# ESP32_base_brd.net
KiCad netlist of a schematic drawn in EAGLE
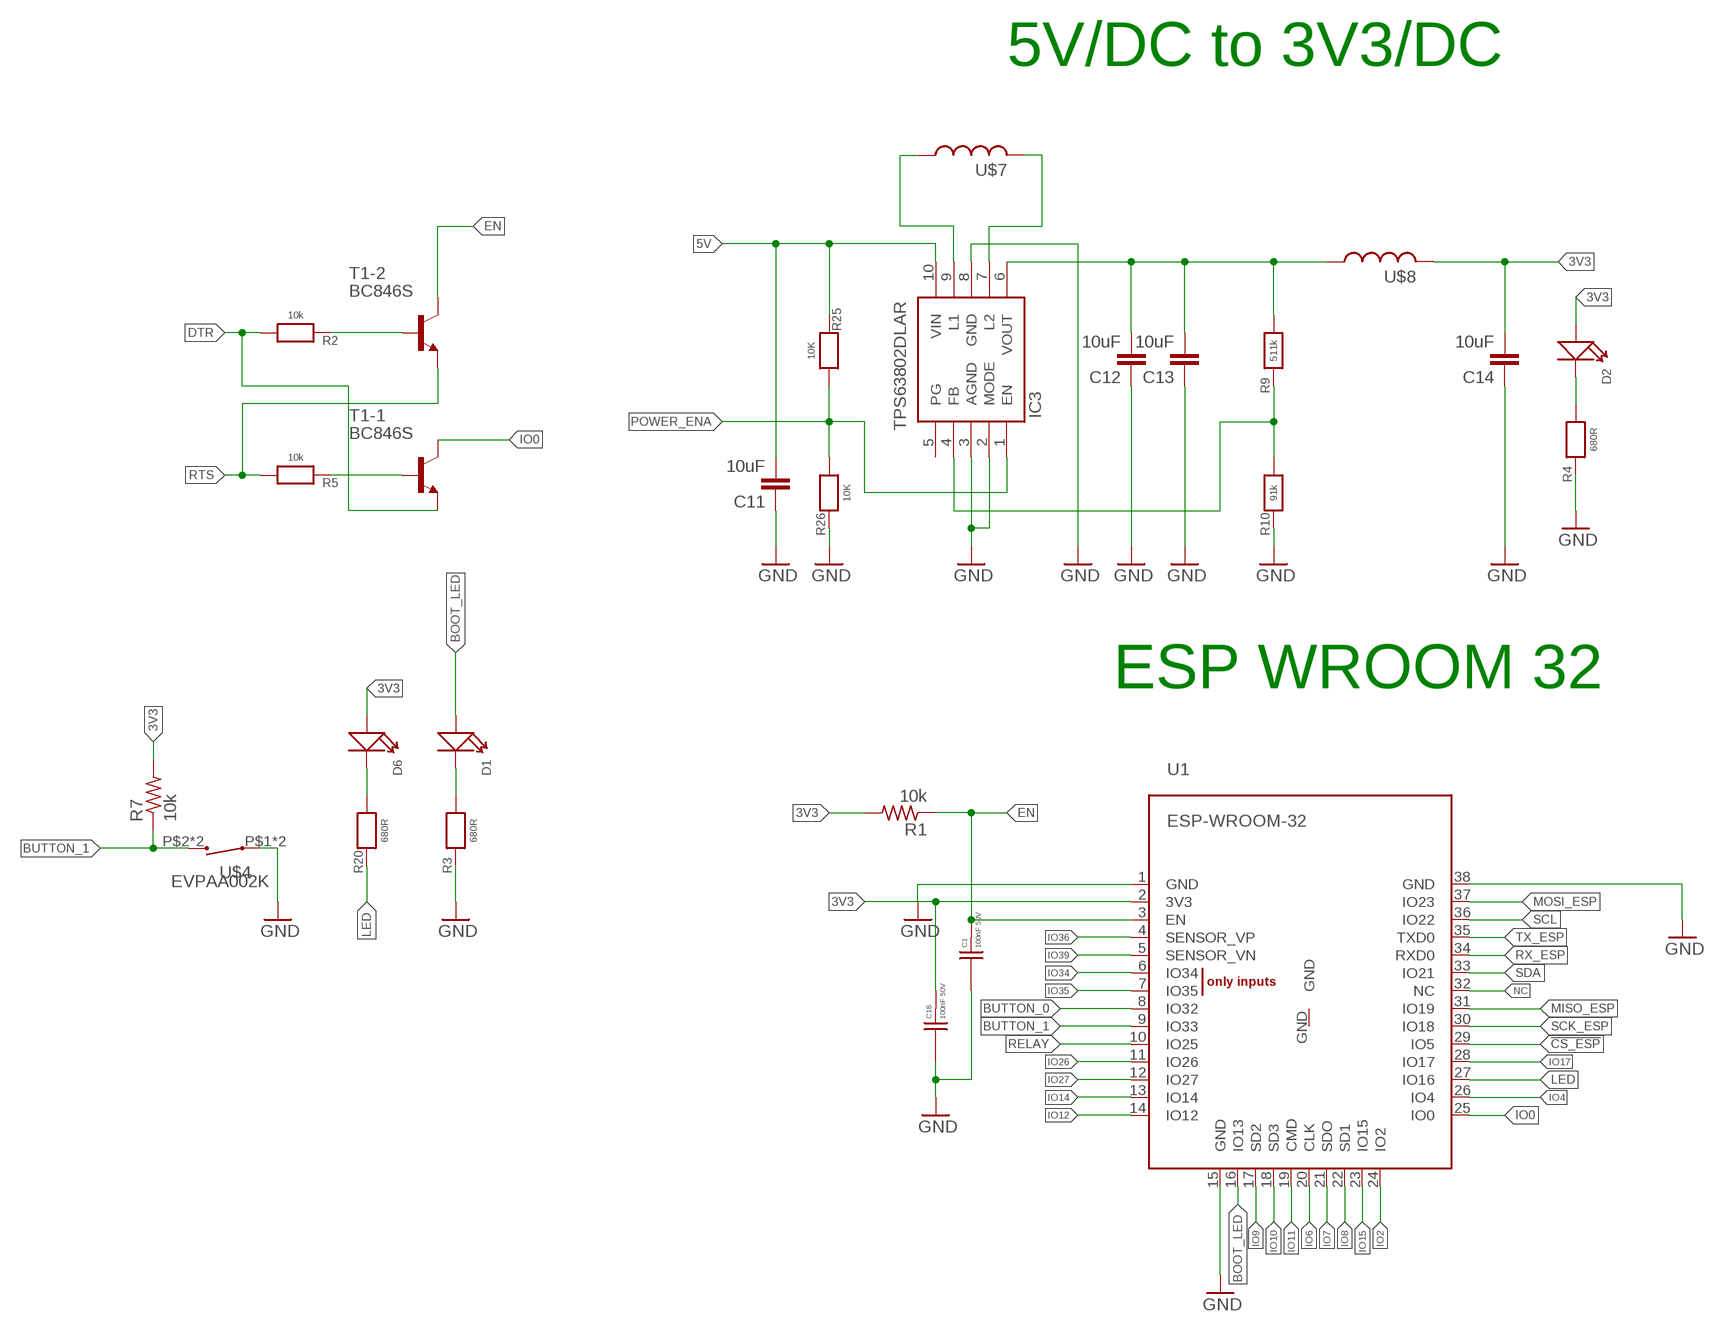
[diagram p0: schematic, sheet 1]

(export (version "E")
  (design (tool "Eeschema 10.0.6"))
  (components
    (comp (ref "C1")
      (value "100nF 50V")
      (footprint "eagle-import:0402")
      (fields (field (name "MPN") "GPC0402104"))
      (libsource (lib "eagle-import") (part "CAPACITOR_CERAMIC_0402_100NF"))
    )
    (comp (ref "C11")
      (value "10uF")
      (footprint "eagle-import:C0603")
      (libsource (lib "eagle-import") (part "C-EUC0603"))
    )
    (comp (ref "C12")
      (value "10uF")
      (footprint "eagle-import:C0603")
      (libsource (lib "eagle-import") (part "C-EUC0603"))
    )
    (comp (ref "C13")
      (value "10uF")
      (footprint "eagle-import:C0603")
      (libsource (lib "eagle-import") (part "C-EUC0603"))
    )
    (comp (ref "C14")
      (value "10uF")
      (footprint "eagle-import:C0603")
      (libsource (lib "eagle-import") (part "C-EUC0603"))
    )
    (comp (ref "C18")
      (value "100nF 50V")
      (footprint "eagle-import:0402")
      (fields (field (name "MPN") "GPC0402104"))
      (libsource (lib "eagle-import") (part "CAPACITOR_CERAMIC_0402_100NF"))
    )
    (comp (ref "D1")
      (value "SMD-LED-YELLOW-DIFFUSED-PURE-WHITE(0402)")
      (footprint "eagle-import:LED-0402")
      (fields (field (name "MPN") "16-219A/T2D-AR2T1QY/3T"))
      (libsource (lib "eagle-import") (part "SMD-LED-YELLOW-DIFFUSED-PURE-WHITE(0402)"))
    )
    (comp (ref "D2")
      (value "SMD-LED-YELLOW-DIFFUSED-PURE-WHITE(0402)")
      (footprint "eagle-import:LED-0402")
      (fields (field (name "MPN") "16-219A/T2D-AR2T1QY/3T"))
      (libsource (lib "eagle-import") (part "SMD-LED-YELLOW-DIFFUSED-PURE-WHITE(0402)"))
    )
    (comp (ref "D6")
      (value "SMD-LED-YELLOW-DIFFUSED-PURE-WHITE(0402)")
      (footprint "eagle-import:LED-0402")
      (fields (field (name "MPN") "16-219A/T2D-AR2T1QY/3T"))
      (libsource (lib "eagle-import") (part "SMD-LED-YELLOW-DIFFUSED-PURE-WHITE(0402)"))
    )
    (comp (ref "IC3")
      (value "TPS63802DLAR")
      (footprint "eagle-import:TPS63802DLAR")
      (libsource (lib "eagle-import") (part "TPS63802DLAR"))
    )
    (comp (ref "R1")
      (value "10k")
      (footprint "eagle-import:R0805")
      (libsource (lib "eagle-import") (part "R-US_R0805"))
    )
    (comp (ref "R2")
      (value "10k")
      (footprint "eagle-import:0402")
      (libsource (lib "eagle-import") (part "vb_R_EC_RESISTOR_0402"))
    )
    (comp (ref "R3")
      (value "680R")
      (footprint "eagle-import:0402")
      (libsource (lib "eagle-import") (part "vb_R_EC_RESISTOR_0402"))
    )
    (comp (ref "R4")
      (value "680R")
      (footprint "eagle-import:0402")
      (libsource (lib "eagle-import") (part "vb_R_EC_RESISTOR_0402"))
    )
    (comp (ref "R5")
      (value "10k")
      (footprint "eagle-import:0402")
      (libsource (lib "eagle-import") (part "vb_R_EC_RESISTOR_0402"))
    )
    (comp (ref "R7")
      (value "10k")
      (footprint "eagle-import:R0805")
      (libsource (lib "eagle-import") (part "R-US_R0805"))
    )
    (comp (ref "R9")
      (value "511k")
      (footprint "eagle-import:0402")
      (libsource (lib "eagle-import") (part "RESISTOR_0402"))
    )
    (comp (ref "R10")
      (value "91k")
      (footprint "eagle-import:0402")
      (libsource (lib "eagle-import") (part "RESISTOR_0402"))
    )
    (comp (ref "R20")
      (value "680R")
      (footprint "eagle-import:0402")
      (libsource (lib "eagle-import") (part "vb_R_EC_RESISTOR_0402"))
    )
    (comp (ref "R25")
      (value "10K")
      (footprint "eagle-import:0402")
      (libsource (lib "eagle-import") (part "RESISTOR_0402"))
    )
    (comp (ref "R26")
      (value "10K")
      (footprint "eagle-import:0402")
      (libsource (lib "eagle-import") (part "RESISTOR_0402"))
    )
    (comp (ref "T1")
      (value "BC846S")
      (footprint "eagle-import:SOT363")
      (fields (field (name "MF") "NXP Semiconductors"))
      (libsource (lib "eagle-import") (part "BC846S"))
    )
    (comp (ref "U$4")
      (value "EVPAA002K")
      (footprint "eagle-import:EVPAA002K")
      (libsource (lib "eagle-import") (part "EVPAA002K"))
    )
    (comp (ref "U$7")
      (value "INDUCTOR_2016")
      (footprint "eagle-import:2016")
      (libsource (lib "eagle-import") (part "INDUCTOR_2016"))
    )
    (comp (ref "U$8")
      (value "INDUCTOR_2016")
      (footprint "eagle-import:2016")
      (libsource (lib "eagle-import") (part "INDUCTOR_2016"))
    )
    (comp (ref "U1")
      (value "ESP-WROOM-32")
      (footprint "eagle-import:ESP-WROOM-32")
      (libsource (lib "eagle-import") (part "ESP-WROOM-32"))
    )
  )
  (nets
    (net (code "1") (name "/~{CS_ESP}") (class "Default")
      (node (ref "U1") (pin "29") (pinfunction "IO5_29") (pintype "bidirectional"))
    )
    (net (code "2") (name "3V3") (class "Default")
      (node (ref "C14") (pin "2") (pinfunction "2_2") (pintype "passive"))
      (node (ref "C18") (pin "2") (pinfunction "2_2") (pintype "passive"))
      (node (ref "D2") (pin "+") (pinfunction "+_+") (pintype "passive"))
      (node (ref "D6") (pin "+") (pinfunction "+_+") (pintype "passive"))
      (node (ref "R1") (pin "2") (pinfunction "2_2") (pintype "passive"))
      (node (ref "R7") (pin "2") (pinfunction "2_2") (pintype "passive"))
      (node (ref "U$8") (pin "2") (pinfunction "2_2") (pintype "passive"))
      (node (ref "U1") (pin "2") (pinfunction "3V3_2") (pintype "bidirectional"))
    )
    (net (code "3") (name "5V") (class "Default")
      (node (ref "C11") (pin "2") (pinfunction "2_2") (pintype "passive"))
      (node (ref "IC3") (pin "10") (pinfunction "VIN_10") (pintype "bidirectional"))
      (node (ref "R25") (pin "1") (pinfunction "1_1") (pintype "passive"))
    )
    (net (code "4") (name "BOOT_LED") (class "Default")
      (node (ref "D1") (pin "+") (pinfunction "+_+") (pintype "passive"))
      (node (ref "U1") (pin "16") (pinfunction "IO13_16") (pintype "bidirectional"))
    )
    (net (code "5") (name "BUTTON_0") (class "Default")
      (node (ref "U1") (pin "8") (pinfunction "IO32_8") (pintype "bidirectional"))
    )
    (net (code "6") (name "BUTTON_1") (class "Default")
      (node (ref "R7") (pin "1") (pinfunction "1_1") (pintype "passive"))
      (node (ref "U$4") (pin "P$2") (pinfunction "2_P$2") (pintype "passive"))
      (node (ref "U$4") (pin "P$4") (pinfunction "2_P$4") (pintype "passive"))
      (node (ref "U1") (pin "9") (pinfunction "IO33_9") (pintype "bidirectional"))
    )
    (net (code "7") (name "DTR") (class "Default")
      (node (ref "R2") (pin "2") (pinfunction "2_2") (pintype "passive"))
      (node (ref "T1") (pin "1") (pinfunction "E_1") (pintype "passive"))
    )
    (net (code "8") (name "EN") (class "Default")
      (node (ref "C1") (pin "2") (pinfunction "2_2") (pintype "passive"))
      (node (ref "R1") (pin "1") (pinfunction "1_1") (pintype "passive"))
      (node (ref "T1") (pin "3") (pinfunction "C_3") (pintype "passive"))
      (node (ref "U1") (pin "3") (pinfunction "EN_3") (pintype "bidirectional"))
    )
    (net (code "9") (name "GND") (class "Default")
      (node (ref "C1") (pin "1") (pinfunction "1_1") (pintype "passive"))
      (node (ref "C11") (pin "1") (pinfunction "1_1") (pintype "passive"))
      (node (ref "C12") (pin "1") (pinfunction "1_1") (pintype "passive"))
      (node (ref "C13") (pin "1") (pinfunction "1_1") (pintype "passive"))
      (node (ref "C14") (pin "1") (pinfunction "1_1") (pintype "passive"))
      (node (ref "C18") (pin "1") (pinfunction "1_1") (pintype "passive"))
      (node (ref "IC3") (pin "2") (pinfunction "MODE_2") (pintype "bidirectional"))
      (node (ref "IC3") (pin "3") (pinfunction "AGND_3") (pintype "bidirectional"))
      (node (ref "IC3") (pin "8") (pinfunction "GND_8") (pintype "bidirectional"))
      (node (ref "R10") (pin "1") (pinfunction "1_1") (pintype "passive"))
      (node (ref "R26") (pin "1") (pinfunction "1_1") (pintype "passive"))
      (node (ref "R3") (pin "1") (pinfunction "1_1") (pintype "passive"))
      (node (ref "R4") (pin "1") (pinfunction "1_1") (pintype "passive"))
      (node (ref "U$4") (pin "P$1") (pinfunction "1_P$1") (pintype "passive"))
      (node (ref "U$4") (pin "P$3") (pinfunction "1_P$3") (pintype "passive"))
      (node (ref "U1") (pin "1") (pinfunction "GND_1") (pintype "bidirectional"))
      (node (ref "U1") (pin "15") (pinfunction "GND_15") (pintype "bidirectional"))
      (node (ref "U1") (pin "38") (pinfunction "GND_38") (pintype "bidirectional"))
    )
    (net (code "10") (name "IO0") (class "Default")
      (node (ref "T1") (pin "6") (pinfunction "C_6") (pintype "passive"))
      (node (ref "U1") (pin "25") (pinfunction "IO0_25") (pintype "bidirectional"))
    )
    (net (code "11") (name "IO2") (class "Default")
      (node (ref "U1") (pin "24") (pinfunction "IO2_24") (pintype "bidirectional"))
    )
    (net (code "12") (name "IO4") (class "Default")
      (node (ref "U1") (pin "26") (pinfunction "IO4_26") (pintype "bidirectional"))
    )
    (net (code "13") (name "IO6") (class "Default")
      (node (ref "U1") (pin "20") (pinfunction "CLK_20") (pintype "bidirectional"))
    )
    (net (code "14") (name "IO7") (class "Default")
      (node (ref "U1") (pin "21") (pinfunction "SDO_21") (pintype "bidirectional"))
    )
    (net (code "15") (name "IO8") (class "Default")
      (node (ref "U1") (pin "22") (pinfunction "SD1_22") (pintype "bidirectional"))
    )
    (net (code "16") (name "IO9") (class "Default")
      (node (ref "U1") (pin "17") (pinfunction "SD2_17") (pintype "bidirectional"))
    )
    (net (code "17") (name "IO10") (class "Default")
      (node (ref "U1") (pin "18") (pinfunction "SD3_18") (pintype "bidirectional"))
    )
    (net (code "18") (name "IO11") (class "Default")
      (node (ref "U1") (pin "19") (pinfunction "CMD_19") (pintype "bidirectional"))
    )
    (net (code "19") (name "IO12") (class "Default")
      (node (ref "U1") (pin "14") (pinfunction "IO12_14") (pintype "bidirectional"))
    )
    (net (code "20") (name "IO14") (class "Default")
      (node (ref "U1") (pin "13") (pinfunction "IO14_13") (pintype "bidirectional"))
    )
    (net (code "21") (name "IO15") (class "Default")
      (node (ref "U1") (pin "23") (pinfunction "IO15_23") (pintype "bidirectional"))
    )
    (net (code "22") (name "IO17") (class "Default")
      (node (ref "U1") (pin "28") (pinfunction "IO17_28") (pintype "bidirectional"))
    )
    (net (code "23") (name "IO26") (class "Default")
      (node (ref "U1") (pin "11") (pinfunction "IO26_11") (pintype "bidirectional"))
    )
    (net (code "24") (name "IO27") (class "Default")
      (node (ref "U1") (pin "12") (pinfunction "IO27_12") (pintype "bidirectional"))
    )
    (net (code "25") (name "IO34") (class "Default")
      (node (ref "U1") (pin "6") (pinfunction "IO34_6") (pintype "input"))
    )
    (net (code "26") (name "IO35") (class "Default")
      (node (ref "U1") (pin "7") (pinfunction "IO35_7") (pintype "input"))
    )
    (net (code "27") (name "IO36") (class "Default")
      (node (ref "U1") (pin "4") (pinfunction "SENSOR_VP_4") (pintype "input"))
    )
    (net (code "28") (name "IO39") (class "Default")
      (node (ref "U1") (pin "5") (pinfunction "SENSOR_VN_5") (pintype "input"))
    )
    (net (code "29") (name "LED") (class "Default")
      (node (ref "R20") (pin "1") (pinfunction "1_1") (pintype "passive"))
      (node (ref "U1") (pin "27") (pinfunction "IO16_27") (pintype "bidirectional"))
    )
    (net (code "30") (name "MISO_ESP") (class "Default")
      (node (ref "U1") (pin "31") (pinfunction "IO19_31") (pintype "bidirectional"))
    )
    (net (code "31") (name "MOSI_ESP") (class "Default")
      (node (ref "U1") (pin "37") (pinfunction "IO23_37") (pintype "bidirectional"))
    )
    (net (code "32") (name "NC") (class "Default")
      (node (ref "U1") (pin "32") (pinfunction "NC_32") (pintype "bidirectional"))
    )
    (net (code "33") (name "Net-(D1-Pad-)") (class "Default")
      (node (ref "D1") (pin "-") (pinfunction "-_-") (pintype "passive"))
      (node (ref "R3") (pin "2") (pinfunction "2_2") (pintype "passive"))
    )
    (net (code "34") (name "Net-(D2-Pad-)") (class "Default")
      (node (ref "D2") (pin "-") (pinfunction "-_-") (pintype "passive"))
      (node (ref "R4") (pin "2") (pinfunction "2_2") (pintype "passive"))
    )
    (net (code "35") (name "Net-(D6-Pad-)") (class "Default")
      (node (ref "D6") (pin "-") (pinfunction "-_-") (pintype "passive"))
      (node (ref "R20") (pin "2") (pinfunction "2_2") (pintype "passive"))
    )
    (net (code "36") (name "Net-(IC3-FB)") (class "Default")
      (node (ref "IC3") (pin "4") (pinfunction "FB_4") (pintype "bidirectional"))
      (node (ref "R10") (pin "2") (pinfunction "2_2") (pintype "passive"))
      (node (ref "R9") (pin "1") (pinfunction "1_1") (pintype "passive"))
    )
    (net (code "37") (name "Net-(IC3-L1)") (class "Default")
      (node (ref "IC3") (pin "9") (pinfunction "L1_9") (pintype "bidirectional"))
      (node (ref "U$7") (pin "1") (pinfunction "1_1") (pintype "passive"))
    )
    (net (code "38") (name "Net-(IC3-L2)") (class "Default")
      (node (ref "IC3") (pin "7") (pinfunction "L2_7") (pintype "bidirectional"))
      (node (ref "U$7") (pin "2") (pinfunction "2_2") (pintype "passive"))
    )
    (net (code "39") (name "Net-(IC3-VOUT)") (class "Default")
      (node (ref "C12") (pin "2") (pinfunction "2_2") (pintype "passive"))
      (node (ref "C13") (pin "2") (pinfunction "2_2") (pintype "passive"))
      (node (ref "IC3") (pin "6") (pinfunction "VOUT_6") (pintype "bidirectional"))
      (node (ref "R9") (pin "2") (pinfunction "2_2") (pintype "passive"))
      (node (ref "U$8") (pin "1") (pinfunction "1_1") (pintype "passive"))
    )
    (net (code "40") (name "Net-(T1A-B)") (class "Default")
      (node (ref "R5") (pin "1") (pinfunction "1_1") (pintype "passive"))
      (node (ref "T1") (pin "2") (pinfunction "B_2") (pintype "passive"))
    )
    (net (code "41") (name "Net-(T1B-B)") (class "Default")
      (node (ref "R2") (pin "1") (pinfunction "1_1") (pintype "passive"))
      (node (ref "T1") (pin "5") (pinfunction "B_5") (pintype "passive"))
    )
    (net (code "42") (name "POWER_ENA") (class "Default")
      (node (ref "IC3") (pin "1") (pinfunction "EN_1") (pintype "bidirectional"))
      (node (ref "R25") (pin "2") (pinfunction "2_2") (pintype "passive"))
      (node (ref "R26") (pin "2") (pinfunction "2_2") (pintype "passive"))
    )
    (net (code "43") (name "RELAY") (class "Default")
      (node (ref "U1") (pin "10") (pinfunction "IO25_10") (pintype "bidirectional"))
    )
    (net (code "44") (name "RTS") (class "Default")
      (node (ref "R5") (pin "2") (pinfunction "2_2") (pintype "passive"))
      (node (ref "T1") (pin "4") (pinfunction "E_4") (pintype "passive"))
    )
    (net (code "45") (name "RX_ESP") (class "Default")
      (node (ref "U1") (pin "34") (pinfunction "RXD0_34") (pintype "bidirectional"))
    )
    (net (code "46") (name "SCK_ESP") (class "Default")
      (node (ref "U1") (pin "30") (pinfunction "IO18_30") (pintype "bidirectional"))
    )
    (net (code "47") (name "SCL") (class "Default")
      (node (ref "U1") (pin "36") (pinfunction "IO22_36") (pintype "bidirectional"))
    )
    (net (code "48") (name "SDA") (class "Default")
      (node (ref "U1") (pin "33") (pinfunction "IO21_33") (pintype "bidirectional"))
    )
    (net (code "49") (name "TX_ESP") (class "Default")
      (node (ref "U1") (pin "35") (pinfunction "TXD0_35") (pintype "bidirectional"))
    )
    (net (code "50") (name "unconnected-(IC3-PG-Pad5)") (class "Default")
      (node (ref "IC3") (pin "5") (pinfunction "PG_5") (pintype "bidirectional"))
    )
    (net (code "51") (name "unconnected-(U1-PadGND)") (class "Default")
      (node (ref "U1") (pin "GND") (pinfunction "GND_GND") (pintype "bidirectional"))
    )
  )
)
